# D1MSHO-autoroute.net
KiCad netlist of a schematic drawn in EAGLE
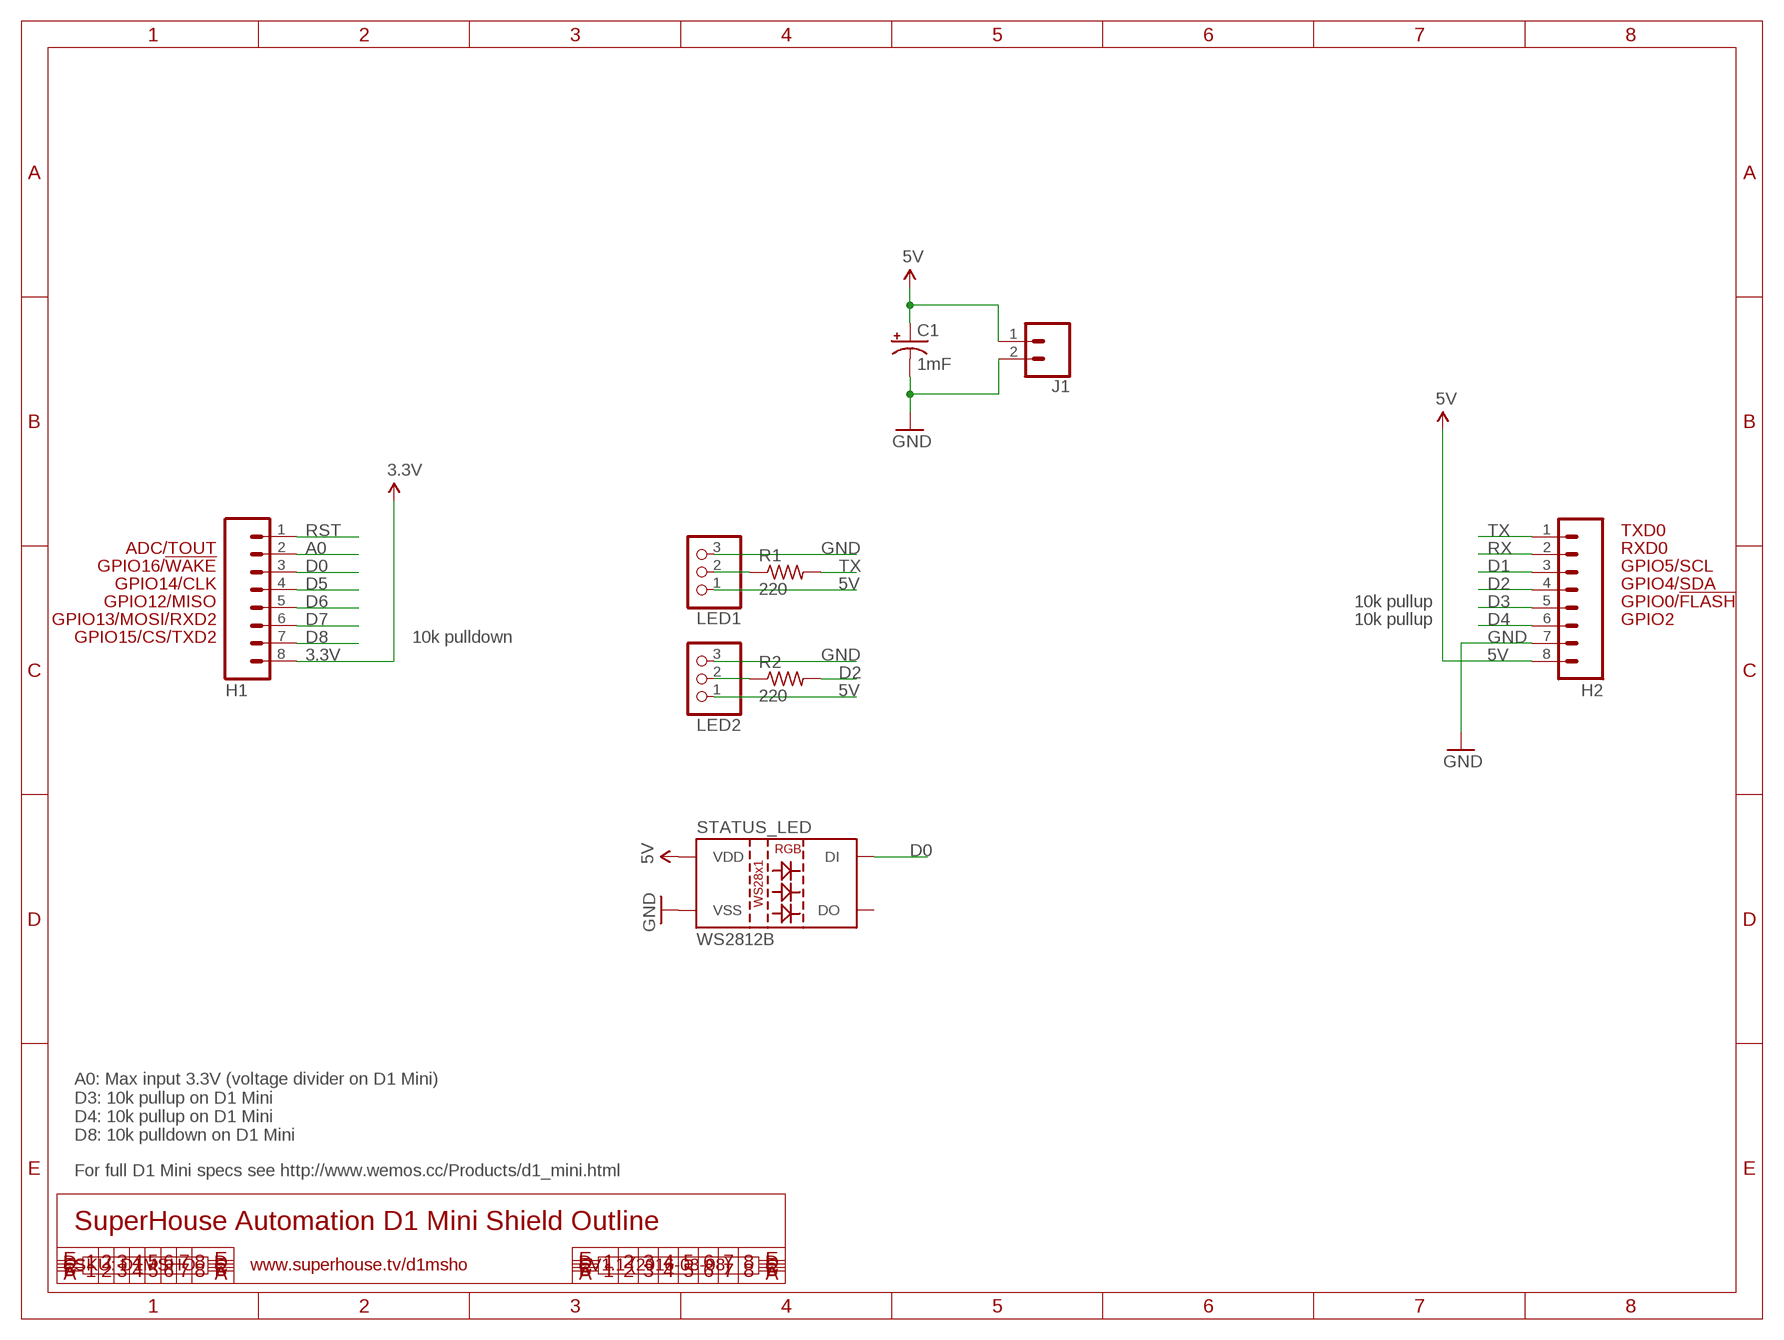
[diagram p0: schematic, sheet 1]

(export (version "E")
  (design (tool "Eeschema 10.0.6"))
  (components
    (comp (ref "C1")
      (value "1mF")
      (footprint "eagle-import:CPOL-RADIAL-5MM-10MM")
      (fields (field (name "SPICEPREFIX") "C"))
      (libsource (lib "eagle-import") (part "1000UF-RADIAL-5MM-25V-20%"))
    )
    (comp (ref "H1")
      (value "M08")
      (footprint "eagle-import:1X08")
      (libsource (lib "eagle-import") (part "M08"))
    )
    (comp (ref "H2")
      (value "M08")
      (footprint "eagle-import:1X08")
      (libsource (lib "eagle-import") (part "M08"))
    )
    (comp (ref "J1")
      (value "CONN_025MM")
      (footprint "eagle-import:SCREWTERMINAL-5MM-2")
      (libsource (lib "eagle-import") (part "CONN_025MM"))
    )
    (comp (ref "LED1")
      (value "PINHD-1X3")
      (footprint "eagle-import:1X03")
      (libsource (lib "eagle-import") (part "PINHD-1X3"))
    )
    (comp (ref "LED2")
      (value "PINHD-1X3")
      (footprint "eagle-import:1X03")
      (libsource (lib "eagle-import") (part "PINHD-1X3"))
    )
    (comp (ref "R1")
      (value "220")
      (footprint "eagle-import:0207_10")
      (libsource (lib "eagle-import") (part "R-US_0207/10"))
    )
    (comp (ref "R2")
      (value "220")
      (footprint "eagle-import:0207_10")
      (libsource (lib "eagle-import") (part "R-US_0207/10"))
    )
    (comp (ref "STATUS_LED")
      (value "WS2812B")
      (footprint "eagle-import:WS2812B")
      (libsource (lib "eagle-import") (part "WS2812B"))
    )
  )
  (nets
    (net (code "1") (name "/A0") (class "Default")
      (node (ref "H1") (pin "2") (pinfunction "2_2") (pintype "passive"))
    )
    (net (code "2") (name "/D0") (class "Default")
      (node (ref "H1") (pin "3") (pinfunction "3_3") (pintype "passive"))
      (node (ref "STATUS_LED") (pin "4") (pinfunction "DI_4") (pintype "bidirectional"))
    )
    (net (code "3") (name "/D1") (class "Default")
      (node (ref "H2") (pin "3") (pinfunction "3_3") (pintype "passive"))
    )
    (net (code "4") (name "/D2") (class "Default")
      (node (ref "H2") (pin "4") (pinfunction "4_4") (pintype "passive"))
      (node (ref "R2") (pin "2") (pinfunction "2_2") (pintype "passive"))
    )
    (net (code "5") (name "/D3") (class "Default")
      (node (ref "H2") (pin "5") (pinfunction "5_5") (pintype "passive"))
    )
    (net (code "6") (name "/D4") (class "Default")
      (node (ref "H2") (pin "6") (pinfunction "6_6") (pintype "passive"))
    )
    (net (code "7") (name "/D5") (class "Default")
      (node (ref "H1") (pin "4") (pinfunction "4_4") (pintype "passive"))
    )
    (net (code "8") (name "/D6") (class "Default")
      (node (ref "H1") (pin "5") (pinfunction "5_5") (pintype "passive"))
    )
    (net (code "9") (name "/D7") (class "Default")
      (node (ref "H1") (pin "6") (pinfunction "6_6") (pintype "passive"))
    )
    (net (code "10") (name "/D8") (class "Default")
      (node (ref "H1") (pin "7") (pinfunction "7_7") (pintype "passive"))
    )
    (net (code "11") (name "/RST") (class "Default")
      (node (ref "H1") (pin "1") (pinfunction "1_1") (pintype "passive"))
    )
    (net (code "12") (name "/RX") (class "Default")
      (node (ref "H2") (pin "2") (pinfunction "2_2") (pintype "passive"))
    )
    (net (code "13") (name "/TX") (class "Default")
      (node (ref "H2") (pin "1") (pinfunction "1_1") (pintype "passive"))
      (node (ref "R1") (pin "2") (pinfunction "2_2") (pintype "passive"))
    )
    (net (code "14") (name "3.3V") (class "Default")
      (node (ref "H1") (pin "8") (pinfunction "8_8") (pintype "passive"))
    )
    (net (code "15") (name "5V") (class "Default")
      (node (ref "C1") (pin "+") (pinfunction "+_+") (pintype "passive"))
      (node (ref "H2") (pin "8") (pinfunction "8_8") (pintype "passive"))
      (node (ref "J1") (pin "1") (pinfunction "1_1") (pintype "passive"))
      (node (ref "LED1") (pin "1") (pinfunction "1_1") (pintype "passive"))
      (node (ref "LED2") (pin "1") (pinfunction "1_1") (pintype "passive"))
      (node (ref "STATUS_LED") (pin "1") (pinfunction "VDD_1") (pintype "bidirectional"))
    )
    (net (code "16") (name "GND") (class "Default")
      (node (ref "C1") (pin "-") (pinfunction "-_-") (pintype "passive"))
      (node (ref "H2") (pin "7") (pinfunction "7_7") (pintype "passive"))
      (node (ref "J1") (pin "2") (pinfunction "2_2") (pintype "passive"))
      (node (ref "LED1") (pin "3") (pinfunction "3_3") (pintype "passive"))
      (node (ref "LED2") (pin "3") (pinfunction "3_3") (pintype "passive"))
      (node (ref "STATUS_LED") (pin "3") (pinfunction "VSS_3") (pintype "bidirectional"))
    )
    (net (code "17") (name "Net-(LED1-Pad2)") (class "Default")
      (node (ref "LED1") (pin "2") (pinfunction "2_2") (pintype "passive"))
      (node (ref "R1") (pin "1") (pinfunction "1_1") (pintype "passive"))
    )
    (net (code "18") (name "Net-(LED2-Pad2)") (class "Default")
      (node (ref "LED2") (pin "2") (pinfunction "2_2") (pintype "passive"))
      (node (ref "R2") (pin "1") (pinfunction "1_1") (pintype "passive"))
    )
    (net (code "19") (name "unconnected-(STATUS_LED-DO-Pad2)") (class "Default")
      (node (ref "STATUS_LED") (pin "2") (pinfunction "DO_2") (pintype "bidirectional"))
    )
  )
)
